# SIM808_dev_Board_V1_0_2.net
KiCad netlist of a schematic drawn in Altium Designer
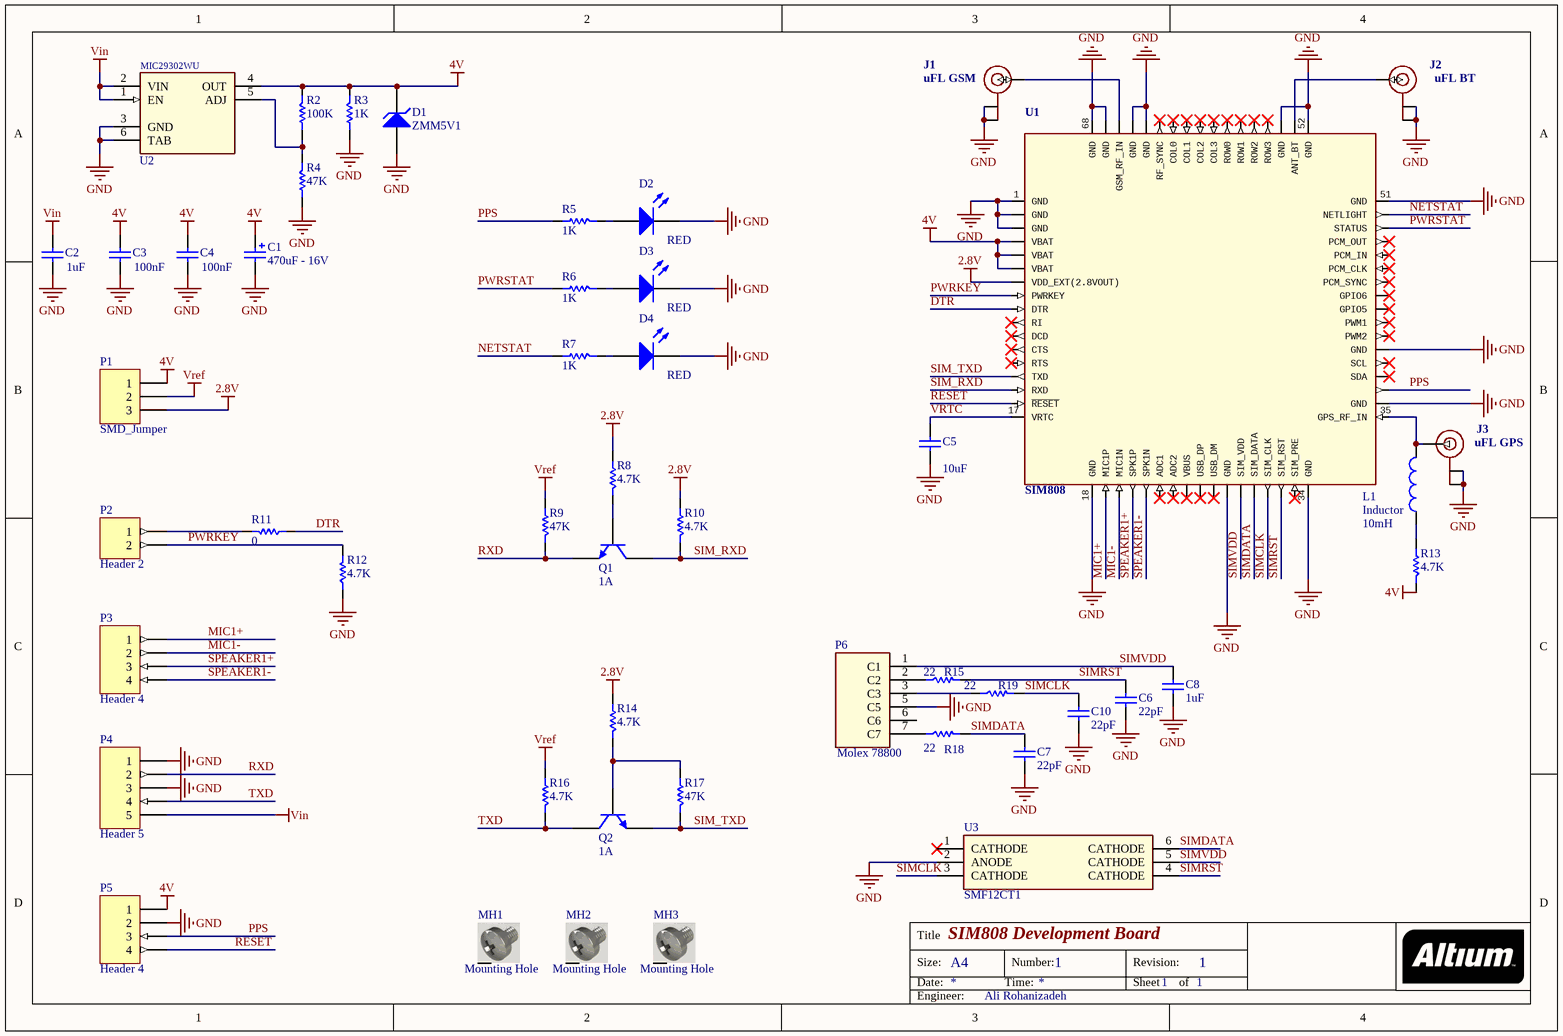
[diagram p0: SIM808 dev Board V1.0.2.SchDoc]

(export (version "E")
  (design (tool "Eeschema 10.0.6"))
  (components
    (comp (ref "C1")
      (value "470uF - 16V")
      (footprint "CAP-D")
      (description "SMD Tantalum Capacitor")
      (fields (field (name "Comment") "470uF") (field (name "PUBLISHER") "Altium Limited"))
      (libsource (lib "Miscellaneous Devices") (part "Cap Pol2"))
    )
    (comp (ref "C2")
      (value "1uF")
      (footprint "CAP0603")
      (description "Capacitor")
      (fields (field (name "PUBLISHER") "Altium Limited"))
      (libsource (lib "Miscellaneous Devices") (part "Cap"))
    )
    (comp (ref "C3")
      (value "100nF")
      (footprint "CAP0603")
      (description "Capacitor")
      (fields (field (name "PUBLISHER") "Altium Limited"))
      (libsource (lib "Miscellaneous Devices") (part "Cap"))
    )
    (comp (ref "C4")
      (value "100nF")
      (footprint "CAP0603")
      (description "Capacitor")
      (fields (field (name "PUBLISHER") "Altium Limited"))
      (libsource (lib "Miscellaneous Devices") (part "Cap"))
    )
    (comp (ref "C5")
      (value "10uF")
      (footprint "CAP1206")
      (description "Capacitor")
      (fields (field (name "PUBLISHER") "Altium Limited"))
      (libsource (lib "Miscellaneous Devices") (part "Cap"))
    )
    (comp (ref "C6")
      (value "22pF")
      (footprint "CAP0603")
      (description "Capacitor")
      (fields (field (name "PUBLISHER") "Altium Limited"))
      (libsource (lib "Miscellaneous Devices") (part "Cap"))
    )
    (comp (ref "C7")
      (value "22pF")
      (footprint "CAP0603")
      (description "Capacitor")
      (fields (field (name "PUBLISHER") "Altium Limited"))
      (libsource (lib "Miscellaneous Devices") (part "Cap"))
    )
    (comp (ref "C8")
      (value "1uF")
      (footprint "CAP0603")
      (description "Capacitor")
      (fields (field (name "PUBLISHER") "Altium Limited"))
      (libsource (lib "Miscellaneous Devices") (part "Cap"))
    )
    (comp (ref "C10")
      (value "22pF")
      (footprint "CAP0603")
      (description "Capacitor")
      (fields (field (name "PUBLISHER") "Altium Limited"))
      (libsource (lib "Miscellaneous Devices") (part "Cap"))
    )
    (comp (ref "D1")
      (value "ZMM5V1")
      (footprint "ZMM5V1")
      (description "ZENER 5.1V-MINI MELF")
      (fields (field (name "PUBLISHER") "Altium Limited"))
      (libsource (lib "Miscellaneous Devices") (part "D Zener"))
    )
    (comp (ref "D2")
      (value "PPS")
      (footprint "LED0603R")
      (description "Typical INFRARED GaAs LED")
      (fields (field (name "COLOR") "RED") (field (name "PUBLISHER") "Altium Limited"))
      (libsource (lib "Miscellaneous Devices") (part "LED0"))
    )
    (comp (ref "D3")
      (value "STA")
      (footprint "LED0603R")
      (description "Typical INFRARED GaAs LED")
      (fields (field (name "COLOR") "RED") (field (name "PUBLISHER") "Altium Limited"))
      (libsource (lib "Miscellaneous Devices") (part "LED0"))
    )
    (comp (ref "D4")
      (value "NET")
      (footprint "LED0603R")
      (description "Typical INFRARED GaAs LED")
      (fields (field (name "COLOR") "RED") (field (name "PUBLISHER") "Altium Limited"))
      (libsource (lib "Miscellaneous Devices") (part "LED0"))
    )
    (comp (ref "J1")
      (value "uFL GSM")
      (footprint "UFL")
      (description "U.FL Antenna Connector")
      (libsource (lib "microbuilder") (part "ANTENNA_U.FL"))
    )
    (comp (ref "J2")
      (value "uFL BT")
      (footprint "UFL")
      (description "U.FL Antenna Connector")
      (libsource (lib "microbuilder") (part "ANTENNA_U.FL"))
    )
    (comp (ref "J3")
      (value "uFL GPS")
      (footprint "UFL")
      (description "U.FL Antenna Connector")
      (libsource (lib "microbuilder") (part "ANTENNA_U.FL"))
    )
    (comp (ref "L1")
      (value "Inductor")
      (footprint "IND0603")
      (fields (field (name "ALTIUM_VALUE") "10mH") (field (name "PUBLISHER") "Altium Limited"))
      (libsource (lib "Miscellaneous Devices") (part "Inductor"))
    )
    (comp (ref "MH1")
      (value "Mounting Hole")
      (footprint "SCREW-3")
      (description "Board Screw With Spacer")
      (libsource (lib "My Library") (part "Board Screw"))
    )
    (comp (ref "MH2")
      (value "Mounting Hole")
      (footprint "SCREW-3")
      (description "Board Screw With Spacer")
      (libsource (lib "My Library") (part "Board Screw"))
    )
    (comp (ref "MH3")
      (value "Mounting Hole")
      (footprint "SCREW-3")
      (description "Board Screw With Spacer")
      (libsource (lib "My Library") (part "Board Screw"))
    )
    (comp (ref "P1")
      (value "SMD_Jumper")
      (footprint "Jumper Selector SMD")
      (description "Header, 3-Pin")
      (fields (field (name "PUBLISHER") "Altium Limited"))
      (libsource (lib "Miscellaneous Connectors") (part "Header 3"))
    )
    (comp (ref "P2")
      (value "Header 2")
      (footprint "HDR1X2")
      (description "Header, 2-Pin")
      (fields (field (name "PUBLISHER") "Altium Limited"))
      (libsource (lib "Miscellaneous Connectors") (part "Header 2"))
    )
    (comp (ref "P3")
      (value "Header 4")
      (footprint "Pin Header 1x4 TH Pitch 2.54mm")
      (description "Header, 4-Pin")
      (fields (field (name "PUBLISHER") "Altium Limited"))
      (libsource (lib "Miscellaneous Connectors") (part "Header 4"))
    )
    (comp (ref "P4")
      (value "Header 5")
      (footprint "Pin Header 1x5 TH Pitch 2.54mm")
      (description "Header, 5-Pin")
      (fields (field (name "PUBLISHER") "Altium Limited"))
      (libsource (lib "Miscellaneous Connectors") (part "Header 5"))
    )
    (comp (ref "P5")
      (value "Header 4")
      (footprint "Pin Header 1x4 TH Pitch 2.54mm")
      (description "Header, 4-Pin")
      (fields (field (name "PUBLISHER") "Altium Limited"))
      (libsource (lib "Miscellaneous Connectors") (part "Header 4"))
    )
    (comp (ref "P6")
      (value "Molex 78800")
      (footprint "MOLEX_78800-0001")
      (fields (field (name "MP") "78800-0001") (field (name "MF") "Molex"))
      (libsource (lib "Library Bank") (part "78800-0001"))
    )
    (comp (ref "Q1")
      (value "1A")
      (footprint "SOT-23")
      (description "Infineon")
      (fields (field (name "PUBLISHER") "Altium Limited"))
      (libsource (lib "FSC Discrete BJT") (part "2N3904"))
    )
    (comp (ref "Q2")
      (value "1A")
      (footprint "SOT-23")
      (description "Infineon")
      (fields (field (name "PUBLISHER") "Altium Limited"))
      (libsource (lib "FSC Discrete BJT") (part "2N3904"))
    )
    (comp (ref "R2")
      (value "100K")
      (footprint "RES0603")
      (description "Resistor")
      (fields (field (name "TOLERANCE") "5%") (field (name "POWER") "1/8 W"))
      (libsource (lib "My Library") (part "Resistor"))
    )
    (comp (ref "R3")
      (value "1K")
      (footprint "RES0603")
      (description "Resistor")
      (fields (field (name "TOLERANCE") "5%") (field (name "POWER") "1/8 W"))
      (libsource (lib "My Library") (part "Resistor"))
    )
    (comp (ref "R4")
      (value "47K")
      (footprint "RES0603")
      (description "Resistor")
      (fields (field (name "TOLERANCE") "5%") (field (name "POWER") "1/8 W"))
      (libsource (lib "My Library") (part "Resistor"))
    )
    (comp (ref "R5")
      (value "1K")
      (footprint "RES0603")
      (description "Resistor")
      (fields (field (name "TOLERANCE") "5%") (field (name "POWER") "1/8 W"))
      (libsource (lib "My Library") (part "Resistor"))
    )
    (comp (ref "R6")
      (value "1K")
      (footprint "RES0603")
      (description "Resistor")
      (fields (field (name "TOLERANCE") "5%") (field (name "POWER") "1/8 W"))
      (libsource (lib "My Library") (part "Resistor"))
    )
    (comp (ref "R7")
      (value "1K")
      (footprint "RES0603")
      (description "Resistor")
      (fields (field (name "TOLERANCE") "5%") (field (name "POWER") "1/8 W"))
      (libsource (lib "My Library") (part "Resistor"))
    )
    (comp (ref "R8")
      (value "4.7K")
      (footprint "RES0603")
      (description "Resistor")
      (fields (field (name "TOLERANCE") "5%") (field (name "POWER") "1/8 W"))
      (libsource (lib "My Library") (part "Resistor"))
    )
    (comp (ref "R9")
      (value "47K")
      (footprint "RES0603")
      (description "Resistor")
      (fields (field (name "TOLERANCE") "5%") (field (name "POWER") "1/8 W"))
      (libsource (lib "My Library") (part "Resistor"))
    )
    (comp (ref "R10")
      (value "4.7K")
      (footprint "RES0603")
      (description "Resistor")
      (fields (field (name "TOLERANCE") "5%") (field (name "POWER") "1/8 W"))
      (libsource (lib "My Library") (part "Resistor"))
    )
    (comp (ref "R11")
      (value "0")
      (footprint "RES0603")
      (description "Resistor")
      (fields (field (name "TOLERANCE") "5%") (field (name "POWER") "1/8 W"))
      (libsource (lib "My Library") (part "Resistor"))
    )
    (comp (ref "R12")
      (value "4.7K")
      (footprint "RES0603")
      (description "Resistor")
      (fields (field (name "TOLERANCE") "5%") (field (name "POWER") "1/8 W"))
      (libsource (lib "My Library") (part "Resistor"))
    )
    (comp (ref "R13")
      (value "4.7K")
      (footprint "RES0603")
      (description "Resistor")
      (fields (field (name "TOLERANCE") "5%") (field (name "POWER") "1/8 W"))
      (libsource (lib "My Library") (part "Resistor"))
    )
    (comp (ref "R14")
      (value "4.7K")
      (footprint "RES0603")
      (description "Resistor")
      (fields (field (name "TOLERANCE") "5%") (field (name "POWER") "1/8 W"))
      (libsource (lib "My Library") (part "Resistor"))
    )
    (comp (ref "R15")
      (value "22")
      (footprint "RES0603")
      (description "Resistor")
      (fields (field (name "TOLERANCE") "5%") (field (name "POWER") "1/8 W"))
      (libsource (lib "My Library") (part "Resistor"))
    )
    (comp (ref "R16")
      (value "4.7K")
      (footprint "RES0603")
      (description "Resistor")
      (fields (field (name "TOLERANCE") "5%") (field (name "POWER") "1/8 W"))
      (libsource (lib "My Library") (part "Resistor"))
    )
    (comp (ref "R17")
      (value "47K")
      (footprint "RES0603")
      (description "Resistor")
      (fields (field (name "TOLERANCE") "5%") (field (name "POWER") "1/8 W"))
      (libsource (lib "My Library") (part "Resistor"))
    )
    (comp (ref "R18")
      (value "22")
      (footprint "RES0603")
      (description "Resistor")
      (fields (field (name "TOLERANCE") "5%") (field (name "POWER") "1/8 W"))
      (libsource (lib "My Library") (part "Resistor"))
    )
    (comp (ref "R19")
      (value "22")
      (footprint "RES0603")
      (description "Resistor")
      (fields (field (name "TOLERANCE") "5%") (field (name "POWER") "1/8 W"))
      (libsource (lib "My Library") (part "Resistor"))
    )
    (comp (ref "U1")
      (value "SIM808")
      (footprint "QFN100P2400X2400X260-68N")
      (libsource (lib "Library Bank") (part "SIM808"))
    )
    (comp (ref "U2")
      (value "MIC29302WU")
      (footprint "TO263-5")
      (description "MIC29302 Series 16 V 3 A Surface Mount Low Dropout Voltage Regulator - TO-263-5")
      (fields (field (name "MP") "MIC29302AWU-TR") (field (name "MF") "Microchip"))
      (libsource (lib "Library Bank") (part "MIC29302WU"))
    )
    (comp (ref "U3")
      (value "SMF12CT1")
      (footprint "INF-PG-SOT-363_M")
      (description "5-Line Transient Voltage Suppressor Array")
      (fields (field (name "MF") "ON Semiconductor"))
      (libsource (lib "Library Bank") (part "SMF12CT1"))
    )
  )
  (nets
    (net (code "1") (name "/DTR") (class "Default")
      (node (ref "R11") (pin "1") (pinfunction "1_1") (pintype "passive"))
      (node (ref "U1") (pin "9") (pinfunction "DTR_9") (pintype "input"))
    )
    (net (code "2") (name "/MIC1+") (class "Default")
      (node (ref "P3") (pin "1") (pinfunction "1_1") (pintype "output"))
      (node (ref "U1") (pin "19") (pinfunction "MIC1P_19") (pintype "input"))
    )
    (net (code "3") (name "/MIC1-") (class "Default")
      (node (ref "P3") (pin "2") (pinfunction "2_2") (pintype "output"))
      (node (ref "U1") (pin "20") (pinfunction "MIC1N_20") (pintype "input"))
    )
    (net (code "4") (name "/NETSTAT") (class "Default")
      (node (ref "R7") (pin "2") (pinfunction "2_2") (pintype "passive"))
      (node (ref "U1") (pin "50") (pinfunction "NETLIGHT_50") (pintype "output"))
    )
    (net (code "5") (name "/PPS") (class "Default")
      (node (ref "P5") (pin "3") (pinfunction "3_3") (pintype "input"))
      (node (ref "R5") (pin "2") (pinfunction "2_2") (pintype "passive"))
      (node (ref "U1") (pin "37") (pinfunction "1PPS_37") (pintype "output"))
    )
    (net (code "6") (name "/PWRKEY") (class "Default")
      (node (ref "P2") (pin "2") (pinfunction "2_2") (pintype "output"))
      (node (ref "R12") (pin "2") (pinfunction "2_2") (pintype "passive"))
      (node (ref "U1") (pin "8") (pinfunction "PWRKEY_8") (pintype "input"))
    )
    (net (code "7") (name "/PWRSTAT") (class "Default")
      (node (ref "R6") (pin "2") (pinfunction "2_2") (pintype "passive"))
      (node (ref "U1") (pin "49") (pinfunction "STATUS_49") (pintype "output"))
    )
    (net (code "8") (name "/RESET") (class "Default")
      (node (ref "P5") (pin "4") (pinfunction "4_4") (pintype "input"))
      (node (ref "U1") (pin "16") (pinfunction "~{RESET}_16") (pintype "input"))
    )
    (net (code "9") (name "/RXD") (class "Default")
      (node (ref "P4") (pin "2") (pinfunction "2_2") (pintype "output"))
      (node (ref "Q1") (pin "2") (pinfunction "E_2") (pintype "passive"))
      (node (ref "R9") (pin "1") (pinfunction "1_1") (pintype "passive"))
    )
    (net (code "10") (name "/SIMCLK") (class "Default")
      (node (ref "C10") (pin "1") (pinfunction "1_1") (pintype "passive"))
      (node (ref "R19") (pin "2") (pinfunction "2_2") (pintype "passive"))
      (node (ref "U1") (pin "31") (pinfunction "SIM_CLK_31") (pintype "output"))
      (node (ref "U3") (pin "3") (pinfunction "CATHODE_3") (pintype "passive"))
    )
    (net (code "11") (name "/SIMDATA") (class "Default")
      (node (ref "C7") (pin "1") (pinfunction "1_1") (pintype "passive"))
      (node (ref "R18") (pin "2") (pinfunction "2_2") (pintype "passive"))
      (node (ref "U1") (pin "30") (pinfunction "SIM_DATA_30") (pintype "bidirectional"))
      (node (ref "U3") (pin "6") (pinfunction "CATHODE_6") (pintype "passive"))
    )
    (net (code "12") (name "/SIMRST") (class "Default")
      (node (ref "C6") (pin "1") (pinfunction "1_1") (pintype "passive"))
      (node (ref "R15") (pin "2") (pinfunction "2_2") (pintype "passive"))
      (node (ref "U1") (pin "32") (pinfunction "SIM_RST_32") (pintype "output"))
      (node (ref "U3") (pin "4") (pinfunction "CATHODE_4") (pintype "passive"))
    )
    (net (code "13") (name "/SIMVDD") (class "Default")
      (node (ref "C8") (pin "1") (pinfunction "1_1") (pintype "passive"))
      (node (ref "P6") (pin "1") (pinfunction "C1_1") (pintype "passive"))
      (node (ref "U1") (pin "29") (pinfunction "SIM_VDD_29") (pintype "power_in"))
      (node (ref "U3") (pin "5") (pinfunction "CATHODE_5") (pintype "passive"))
    )
    (net (code "14") (name "/SIM_RXD") (class "Default")
      (node (ref "Q1") (pin "3") (pinfunction "C_3") (pintype "passive"))
      (node (ref "R10") (pin "1") (pinfunction "1_1") (pintype "passive"))
      (node (ref "U1") (pin "15") (pinfunction "RXD_15") (pintype "input"))
    )
    (net (code "15") (name "/SIM_TXD") (class "Default")
      (node (ref "Q2") (pin "2") (pinfunction "E_2") (pintype "passive"))
      (node (ref "R17") (pin "1") (pinfunction "1_1") (pintype "passive"))
      (node (ref "U1") (pin "14") (pinfunction "TXD_14") (pintype "output"))
    )
    (net (code "16") (name "/SPEAKER1+") (class "Default")
      (node (ref "P3") (pin "3") (pinfunction "3_3") (pintype "input"))
      (node (ref "U1") (pin "21") (pinfunction "SPK1P_21") (pintype "output"))
    )
    (net (code "17") (name "/SPEAKER1-") (class "Default")
      (node (ref "P3") (pin "4") (pinfunction "4_4") (pintype "input"))
      (node (ref "U1") (pin "22") (pinfunction "SPK1N_22") (pintype "output"))
    )
    (net (code "18") (name "/TXD") (class "Default")
      (node (ref "P4") (pin "4") (pinfunction "4_4") (pintype "input"))
      (node (ref "Q2") (pin "3") (pinfunction "C_3") (pintype "passive"))
      (node (ref "R16") (pin "1") (pinfunction "1_1") (pintype "passive"))
    )
    (net (code "19") (name "/VRTC") (class "Default")
      (node (ref "C5") (pin "1") (pinfunction "1_1") (pintype "passive"))
      (node (ref "U1") (pin "17") (pinfunction "VRTC_17") (pintype "power_in"))
    )
    (net (code "20") (name "2.8V") (class "Default")
      (node (ref "P1") (pin "3") (pinfunction "3_3") (pintype "passive"))
      (node (ref "R10") (pin "2") (pinfunction "2_2") (pintype "passive"))
      (node (ref "R14") (pin "2") (pinfunction "2_2") (pintype "passive"))
      (node (ref "R8") (pin "2") (pinfunction "2_2") (pintype "passive"))
      (node (ref "U1") (pin "7") (pinfunction "VDD_EXT(2.8VOUT)_7") (pintype "power_in"))
    )
    (net (code "21") (name "4V") (class "Default")
      (node (ref "C1") (pin "1") (pinfunction "1_1") (pintype "passive"))
      (node (ref "C3") (pin "1") (pinfunction "1_1") (pintype "passive"))
      (node (ref "C4") (pin "1") (pinfunction "1_1") (pintype "passive"))
      (node (ref "D1") (pin "2") (pinfunction "K_2") (pintype "passive"))
      (node (ref "P1") (pin "1") (pinfunction "1_1") (pintype "passive"))
      (node (ref "P5") (pin "1") (pinfunction "1_1") (pintype "output"))
      (node (ref "R13") (pin "1") (pinfunction "1_1") (pintype "passive"))
      (node (ref "R2") (pin "1") (pinfunction "1_1") (pintype "passive"))
      (node (ref "R3") (pin "1") (pinfunction "1_1") (pintype "passive"))
      (node (ref "U1") (pin "4") (pinfunction "VBAT_4") (pintype "power_in"))
      (node (ref "U1") (pin "5") (pinfunction "VBAT_5") (pintype "power_in"))
      (node (ref "U1") (pin "6") (pinfunction "VBAT_6") (pintype "power_in"))
      (node (ref "U2") (pin "4") (pinfunction "OUT_4") (pintype "power_in"))
    )
    (net (code "22") (name "GND") (class "Default")
      (node (ref "C1") (pin "2") (pinfunction "2_2") (pintype "passive"))
      (node (ref "C10") (pin "2") (pinfunction "2_2") (pintype "passive"))
      (node (ref "C2") (pin "2") (pinfunction "2_2") (pintype "passive"))
      (node (ref "C3") (pin "2") (pinfunction "2_2") (pintype "passive"))
      (node (ref "C4") (pin "2") (pinfunction "2_2") (pintype "passive"))
      (node (ref "C5") (pin "2") (pinfunction "2_2") (pintype "passive"))
      (node (ref "C6") (pin "2") (pinfunction "2_2") (pintype "passive"))
      (node (ref "C7") (pin "2") (pinfunction "2_2") (pintype "passive"))
      (node (ref "C8") (pin "2") (pinfunction "2_2") (pintype "passive"))
      (node (ref "D1") (pin "1") (pinfunction "A_1") (pintype "passive"))
      (node (ref "D2") (pin "2") (pinfunction "K_2") (pintype "passive"))
      (node (ref "D3") (pin "2") (pinfunction "K_2") (pintype "passive"))
      (node (ref "D4") (pin "2") (pinfunction "K_2") (pintype "passive"))
      (node (ref "J1") (pin "1") (pinfunction "GND_1") (pintype "passive"))
      (node (ref "J1") (pin "2") (pinfunction "GND_2") (pintype "passive"))
      (node (ref "J2") (pin "1") (pinfunction "GND_1") (pintype "passive"))
      (node (ref "J2") (pin "2") (pinfunction "GND_2") (pintype "passive"))
      (node (ref "J3") (pin "1") (pinfunction "GND_1") (pintype "passive"))
      (node (ref "J3") (pin "2") (pinfunction "GND_2") (pintype "passive"))
      (node (ref "P4") (pin "1") (pinfunction "1_1") (pintype "power_in"))
      (node (ref "P4") (pin "3") (pinfunction "3_3") (pintype "power_in"))
      (node (ref "P5") (pin "2") (pinfunction "2_2") (pintype "output"))
      (node (ref "P6") (pin "5") (pinfunction "C5_5") (pintype "passive"))
      (node (ref "R12") (pin "1") (pinfunction "1_1") (pintype "passive"))
      (node (ref "R3") (pin "2") (pinfunction "2_2") (pintype "passive"))
      (node (ref "R4") (pin "2") (pinfunction "2_2") (pintype "passive"))
      (node (ref "U1") (pin "1") (pinfunction "GND_1") (pintype "power_in"))
      (node (ref "U1") (pin "18") (pinfunction "GND_18") (pintype "power_in"))
      (node (ref "U1") (pin "2") (pinfunction "GND_2") (pintype "power_in"))
      (node (ref "U1") (pin "28") (pinfunction "GND_28") (pintype "power_in"))
      (node (ref "U1") (pin "3") (pinfunction "GND_3") (pintype "power_in"))
      (node (ref "U1") (pin "34") (pinfunction "GND_34") (pintype "power_in"))
      (node (ref "U1") (pin "36") (pinfunction "GND_36") (pintype "power_in"))
      (node (ref "U1") (pin "40") (pinfunction "GND_40") (pintype "power_in"))
      (node (ref "U1") (pin "51") (pinfunction "GND_51") (pintype "power_in"))
      (node (ref "U1") (pin "52") (pinfunction "GND_52") (pintype "power_in"))
      (node (ref "U1") (pin "54") (pinfunction "GND_54") (pintype "power_in"))
      (node (ref "U1") (pin "64") (pinfunction "GND_64") (pintype "power_in"))
      (node (ref "U1") (pin "65") (pinfunction "GND_65") (pintype "power_in"))
      (node (ref "U1") (pin "67") (pinfunction "GND_67") (pintype "power_in"))
      (node (ref "U1") (pin "68") (pinfunction "GND_68") (pintype "power_in"))
      (node (ref "U2") (pin "3") (pinfunction "GND_3") (pintype "power_in"))
      (node (ref "U2") (pin "6") (pinfunction "TAB_6") (pintype "power_in"))
      (node (ref "U3") (pin "2") (pinfunction "ANODE_2") (pintype "passive"))
    )
    (net (code "23") (name "Net-(D2-A)") (class "Default")
      (node (ref "D2") (pin "1") (pinfunction "A_1") (pintype "passive"))
      (node (ref "R5") (pin "1") (pinfunction "1_1") (pintype "passive"))
    )
    (net (code "24") (name "Net-(D3-A)") (class "Default")
      (node (ref "D3") (pin "1") (pinfunction "A_1") (pintype "passive"))
      (node (ref "R6") (pin "1") (pinfunction "1_1") (pintype "passive"))
    )
    (net (code "25") (name "Net-(D4-A)") (class "Default")
      (node (ref "D4") (pin "1") (pinfunction "A_1") (pintype "passive"))
      (node (ref "R7") (pin "1") (pinfunction "1_1") (pintype "passive"))
    )
    (net (code "26") (name "Net-(J1-SIGNAL)") (class "Default")
      (node (ref "J1") (pin "3") (pinfunction "SIGNAL_3") (pintype "bidirectional"))
      (node (ref "U1") (pin "66") (pinfunction "GSM_RF_IN_66") (pintype "bidirectional"))
    )
    (net (code "27") (name "Net-(J2-SIGNAL)") (class "Default")
      (node (ref "J2") (pin "3") (pinfunction "SIGNAL_3") (pintype "bidirectional"))
      (node (ref "U1") (pin "53") (pinfunction "ANT_BT_53") (pintype "bidirectional"))
    )
    (net (code "28") (name "Net-(J3-SIGNAL)") (class "Default")
      (node (ref "J3") (pin "3") (pinfunction "SIGNAL_3") (pintype "bidirectional"))
      (node (ref "L1") (pin "2") (pinfunction "2_2") (pintype "passive"))
      (node (ref "U1") (pin "35") (pinfunction "GPS_RF_IN_35") (pintype "input"))
    )
    (net (code "29") (name "Net-(L1-Pad1)") (class "Default")
      (node (ref "L1") (pin "1") (pinfunction "1_1") (pintype "passive"))
      (node (ref "R13") (pin "2") (pinfunction "2_2") (pintype "passive"))
    )
    (net (code "30") (name "Net-(P2-Pad1)") (class "Default")
      (node (ref "P2") (pin "1") (pinfunction "1_1") (pintype "output"))
      (node (ref "R11") (pin "2") (pinfunction "2_2") (pintype "passive"))
    )
    (net (code "31") (name "Net-(P6-C2)") (class "Default")
      (node (ref "P6") (pin "2") (pinfunction "C2_2") (pintype "passive"))
      (node (ref "R15") (pin "1") (pinfunction "1_1") (pintype "passive"))
    )
    (net (code "32") (name "Net-(P6-C3)") (class "Default")
      (node (ref "P6") (pin "3") (pinfunction "C3_3") (pintype "passive"))
      (node (ref "R19") (pin "1") (pinfunction "1_1") (pintype "passive"))
    )
    (net (code "33") (name "Net-(P6-C7)") (class "Default")
      (node (ref "P6") (pin "7") (pinfunction "C7_7") (pintype "passive"))
      (node (ref "R18") (pin "1") (pinfunction "1_1") (pintype "passive"))
    )
    (net (code "34") (name "Net-(Q1-B)") (class "Default")
      (node (ref "Q1") (pin "1") (pinfunction "B_1") (pintype "passive"))
      (node (ref "R8") (pin "1") (pinfunction "1_1") (pintype "passive"))
    )
    (net (code "35") (name "Net-(Q2-B)") (class "Default")
      (node (ref "Q2") (pin "1") (pinfunction "B_1") (pintype "passive"))
      (node (ref "R14") (pin "1") (pinfunction "1_1") (pintype "passive"))
      (node (ref "R17") (pin "2") (pinfunction "2_2") (pintype "passive"))
    )
    (net (code "36") (name "Net-(U2-ADJ)") (class "Default")
      (node (ref "R2") (pin "2") (pinfunction "2_2") (pintype "passive"))
      (node (ref "R4") (pin "1") (pinfunction "1_1") (pintype "passive"))
      (node (ref "U2") (pin "5") (pinfunction "ADJ_5") (pintype "power_in"))
    )
    (net (code "37") (name "Vin") (class "Default")
      (node (ref "C2") (pin "1") (pinfunction "1_1") (pintype "passive"))
      (node (ref "P4") (pin "5") (pinfunction "5_5") (pintype "power_in"))
      (node (ref "U2") (pin "1") (pinfunction "EN_1") (pintype "input"))
      (node (ref "U2") (pin "2") (pinfunction "VIN_2") (pintype "power_in"))
    )
    (net (code "38") (name "Vref") (class "Default")
      (node (ref "P1") (pin "2") (pinfunction "2_2") (pintype "passive"))
      (node (ref "R16") (pin "2") (pinfunction "2_2") (pintype "passive"))
      (node (ref "R9") (pin "2") (pinfunction "2_2") (pintype "passive"))
    )
    (net (code "39") (name "unconnected-(MH1-PadS)") (class "Default")
      (node (ref "MH1") (pin "S") (pinfunction "S_S") (pintype "passive"))
    )
    (net (code "40") (name "unconnected-(MH2-PadS)") (class "Default")
      (node (ref "MH2") (pin "S") (pinfunction "S_S") (pintype "passive"))
    )
    (net (code "41") (name "unconnected-(MH3-PadS)") (class "Default")
      (node (ref "MH3") (pin "S") (pinfunction "S_S") (pintype "passive"))
    )
    (net (code "42") (name "unconnected-(P6-C6-Pad6)") (class "Default")
      (node (ref "P6") (pin "6") (pinfunction "C6_6") (pintype "passive"))
    )
    (net (code "43") (name "unconnected-(U1-ADC1-Pad23)") (class "Default")
      (node (ref "U1") (pin "23") (pinfunction "ADC1_23") (pintype "input+no_connect"))
    )
    (net (code "44") (name "unconnected-(U1-ADC2-Pad24)") (class "Default")
      (node (ref "U1") (pin "24") (pinfunction "ADC2_24") (pintype "input+no_connect"))
    )
    (net (code "45") (name "unconnected-(U1-COL0-Pad62)") (class "Default")
      (node (ref "U1") (pin "62") (pinfunction "COL0_62") (pintype "input+no_connect"))
    )
    (net (code "46") (name "unconnected-(U1-COL1-Pad61)") (class "Default")
      (node (ref "U1") (pin "61") (pinfunction "COL1_61") (pintype "input+no_connect"))
    )
    (net (code "47") (name "unconnected-(U1-COL2-Pad60)") (class "Default")
      (node (ref "U1") (pin "60") (pinfunction "COL2_60") (pintype "input+no_connect"))
    )
    (net (code "48") (name "unconnected-(U1-COL3-Pad59)") (class "Default")
      (node (ref "U1") (pin "59") (pinfunction "COL3_59") (pintype "input+no_connect"))
    )
    (net (code "49") (name "unconnected-(U1-CTS-Pad12)") (class "Default")
      (node (ref "U1") (pin "12") (pinfunction "CTS_12") (pintype "output+no_connect"))
    )
    (net (code "50") (name "unconnected-(U1-DCD-Pad11)") (class "Default")
      (node (ref "U1") (pin "11") (pinfunction "DCD_11") (pintype "output+no_connect"))
    )
    (net (code "51") (name "unconnected-(U1-GPIO5-Pad43)") (class "Default")
      (node (ref "U1") (pin "43") (pinfunction "GPIO5_43") (pintype "bidirectional+no_connect"))
    )
    (net (code "52") (name "unconnected-(U1-GPIO6-Pad44)") (class "Default")
      (node (ref "U1") (pin "44") (pinfunction "GPIO6_44") (pintype "bidirectional+no_connect"))
    )
    (net (code "53") (name "unconnected-(U1-PCM_CLK-Pad46)") (class "Default")
      (node (ref "U1") (pin "46") (pinfunction "PCM_CLK_46") (pintype "input+no_connect"))
    )
    (net (code "54") (name "unconnected-(U1-PCM_IN-Pad47)") (class "Default")
      (node (ref "U1") (pin "47") (pinfunction "PCM_IN_47") (pintype "input+no_connect"))
    )
    (net (code "55") (name "unconnected-(U1-PCM_OUT-Pad48)") (class "Default")
      (node (ref "U1") (pin "48") (pinfunction "PCM_OUT_48") (pintype "output+no_connect"))
    )
    (net (code "56") (name "unconnected-(U1-PCM_SYNC-Pad45)") (class "Default")
      (node (ref "U1") (pin "45") (pinfunction "PCM_SYNC_45") (pintype "output+no_connect"))
    )
    (net (code "57") (name "unconnected-(U1-PWM1-Pad42)") (class "Default")
      (node (ref "U1") (pin "42") (pinfunction "PWM1_42") (pintype "output+no_connect"))
    )
    (net (code "58") (name "unconnected-(U1-PWM2-Pad41)") (class "Default")
      (node (ref "U1") (pin "41") (pinfunction "PWM2_41") (pintype "output+no_connect"))
    )
    (net (code "59") (name "unconnected-(U1-RF_SYNC-Pad63)") (class "Default")
      (node (ref "U1") (pin "63") (pinfunction "RF_SYNC_63") (pintype "output+no_connect"))
    )
    (net (code "60") (name "unconnected-(U1-RI-Pad10)") (class "Default")
      (node (ref "U1") (pin "10") (pinfunction "RI_10") (pintype "output+no_connect"))
    )
    (net (code "61") (name "unconnected-(U1-ROW0-Pad58)") (class "Default")
      (node (ref "U1") (pin "58") (pinfunction "ROW0_58") (pintype "output+no_connect"))
    )
    (net (code "62") (name "unconnected-(U1-ROW1-Pad57)") (class "Default")
      (node (ref "U1") (pin "57") (pinfunction "ROW1_57") (pintype "output+no_connect"))
    )
    (net (code "63") (name "unconnected-(U1-ROW2-Pad56)") (class "Default")
      (node (ref "U1") (pin "56") (pinfunction "ROW2_56") (pintype "output+no_connect"))
    )
    (net (code "64") (name "unconnected-(U1-ROW3-Pad55)") (class "Default")
      (node (ref "U1") (pin "55") (pinfunction "ROW3_55") (pintype "output+no_connect"))
    )
    (net (code "65") (name "unconnected-(U1-RTS-Pad13)") (class "Default")
      (node (ref "U1") (pin "13") (pinfunction "RTS_13") (pintype "input+no_connect"))
    )
    (net (code "66") (name "unconnected-(U1-SCL-Pad39)") (class "Default")
      (node (ref "U1") (pin "39") (pinfunction "SCL_39") (pintype "output+no_connect"))
    )
    (net (code "67") (name "unconnected-(U1-SDA-Pad38)") (class "Default")
      (node (ref "U1") (pin "38") (pinfunction "SDA_38") (pintype "bidirectional+no_connect"))
    )
    (net (code "68") (name "unconnected-(U1-SIM_PRE-Pad33)") (class "Default")
      (node (ref "U1") (pin "33") (pinfunction "SIM_PRE_33") (pintype "input+no_connect"))
    )
    (net (code "69") (name "unconnected-(U1-USB_DM-Pad27)") (class "Default")
      (node (ref "U1") (pin "27") (pinfunction "USB_DM_27") (pintype "bidirectional+no_connect"))
    )
    (net (code "70") (name "unconnected-(U1-USB_DP-Pad26)") (class "Default")
      (node (ref "U1") (pin "26") (pinfunction "USB_DP_26") (pintype "bidirectional+no_connect"))
    )
    (net (code "71") (name "unconnected-(U1-VBUS-Pad25)") (class "Default")
      (node (ref "U1") (pin "25") (pinfunction "VBUS_25") (pintype "power_in+no_connect"))
    )
    (net (code "72") (name "unconnected-(U3-CATHODE-Pad1)") (class "Default")
      (node (ref "U3") (pin "1") (pinfunction "CATHODE_1") (pintype "passive+no_connect"))
    )
  )
)
